# mapleSDuino-V0_1_007-eagle7.net
KiCad netlist of a schematic drawn in EAGLE
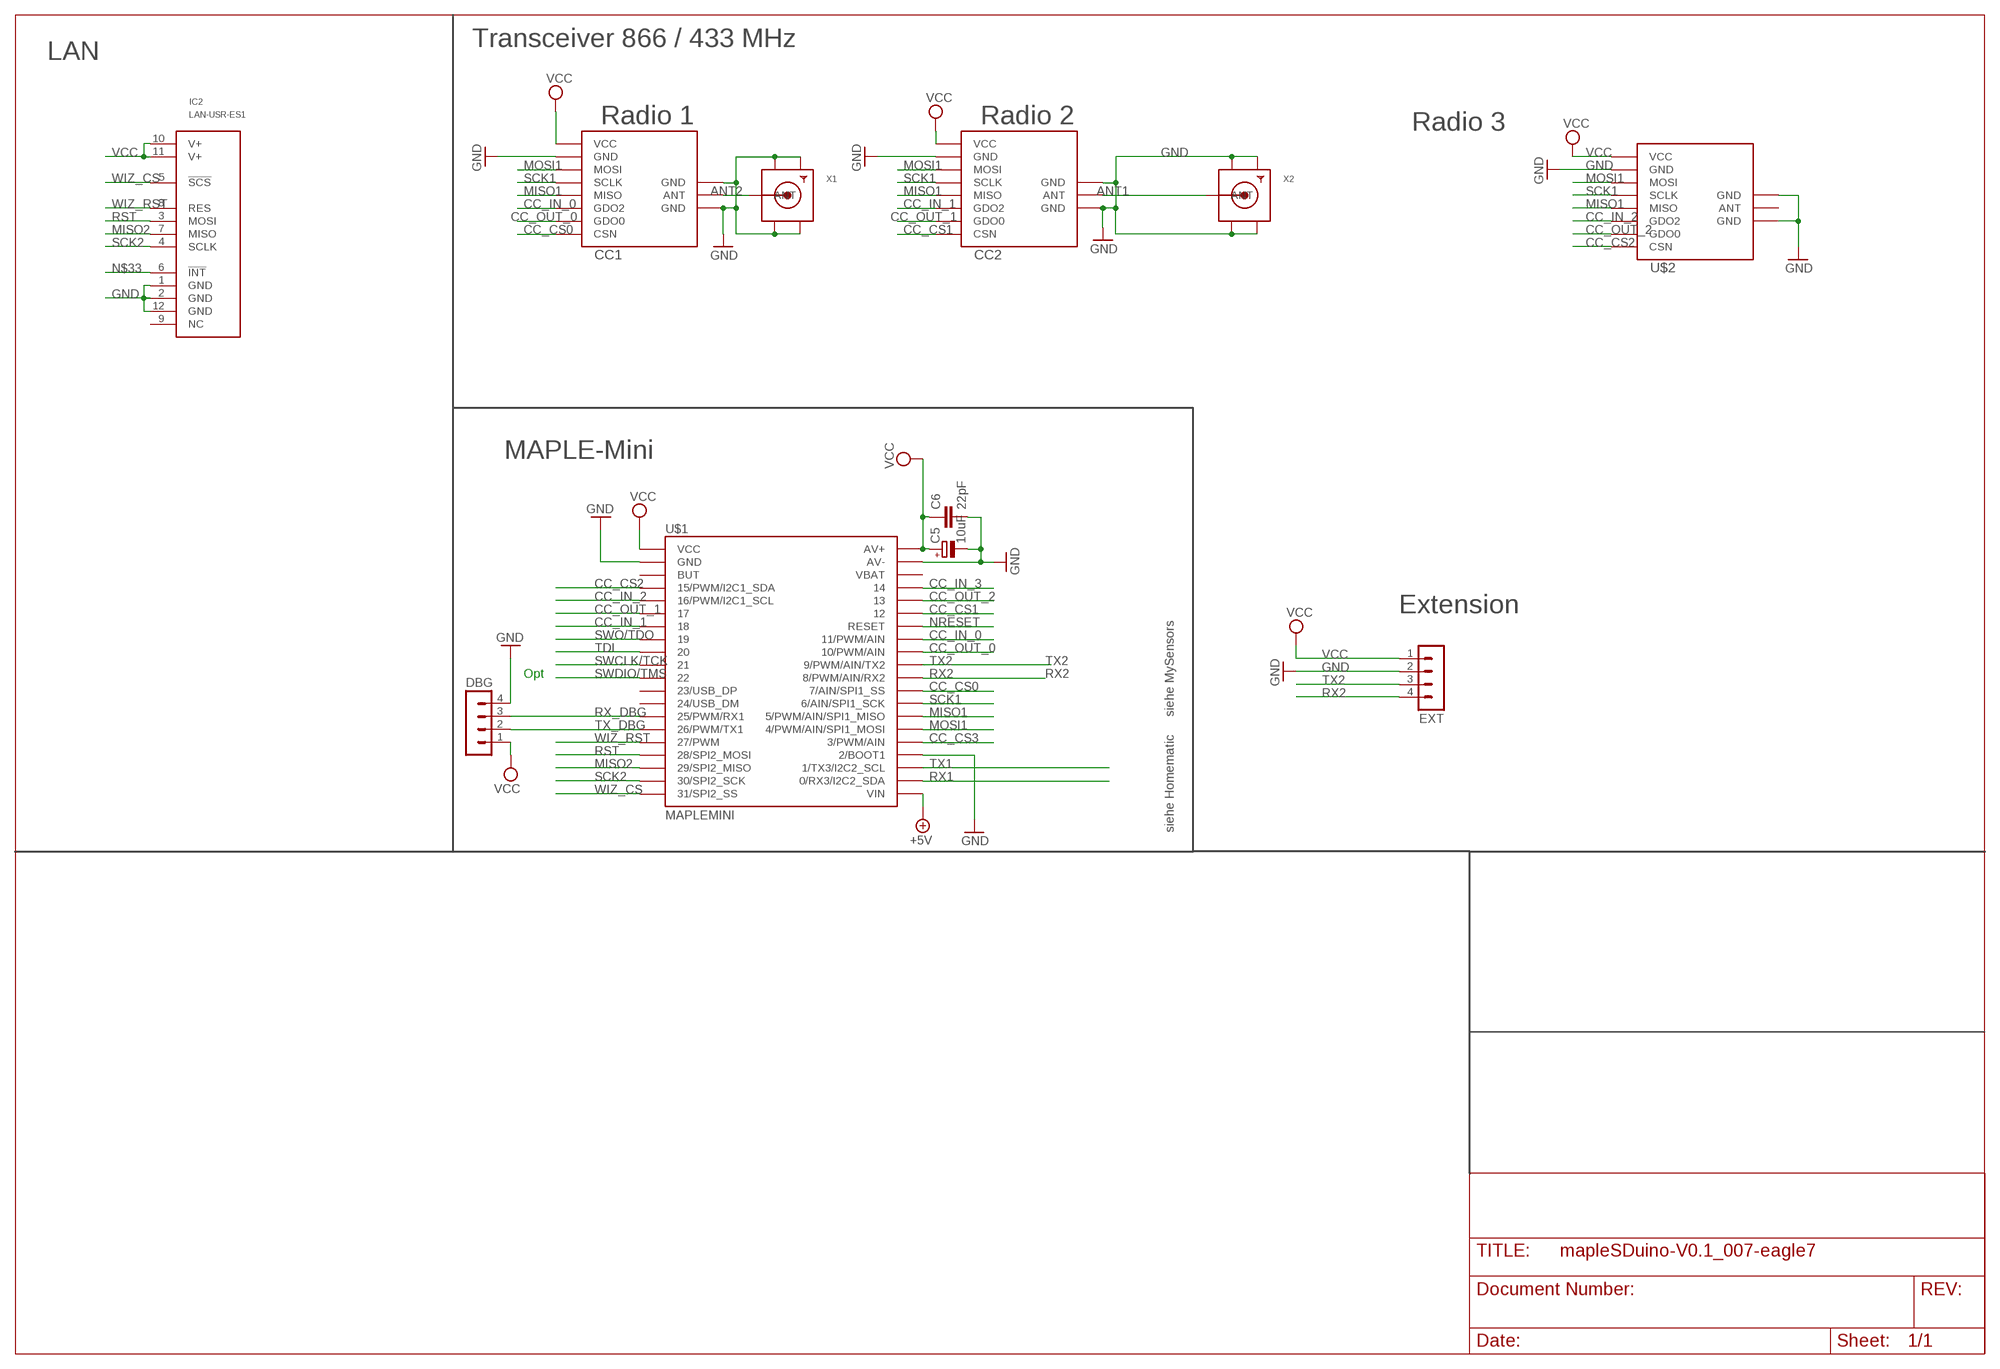
[diagram p0: schematic, sheet 1]

(export (version "E")
  (design (tool "Eeschema 10.0.6"))
  (components
    (comp (ref "C5")
      (value "10uF")
      (footprint "eagle-import:R_2012-12W")
      (libsource (lib "eagle-import") (part "CPOL-EUR/2012-12W"))
    )
    (comp (ref "C6")
      (value "22pF")
      (footprint "eagle-import:C0805")
      (libsource (lib "eagle-import") (part "C-EUC0805"))
    )
    (comp (ref "CC1")
      (value "CC1101")
      (footprint "eagle-import:CC1101_MODULE1_SMD")
      (libsource (lib "eagle-import") (part "wireless_CC1101_MODULE1SMD"))
    )
    (comp (ref "CC2")
      (value "CC1101_MODULE1SMD")
      (footprint "eagle-import:CC1101_MODULE1_SMD")
      (libsource (lib "eagle-import") (part "wireless_CC1101_MODULE1SMD"))
    )
    (comp (ref "DBG")
      (value "MA04-1")
      (footprint "eagle-import:MA04-1")
      (libsource (lib "eagle-import") (part "MA04-1"))
    )
    (comp (ref "EXT")
      (value "MA04-1")
      (footprint "eagle-import:MA04-1")
      (libsource (lib "eagle-import") (part "MA04-1"))
    )
    (comp (ref "IC2")
      (value "LAN-USR-ES1")
      (footprint "eagle-import:USR-ES1")
      (libsource (lib "eagle-import") (part "LAN-USR-ES1"))
    )
    (comp (ref "U$1")
      (value "MAPLEMINI")
      (footprint "eagle-import:20-DIP")
      (libsource (lib "eagle-import") (part "MAPLEMINI"))
    )
    (comp (ref "U$2")
      (value "CC1101_MODULE1DIL_BIG")
      (footprint "eagle-import:CC1101_MODULE1_DIL-2")
      (libsource (lib "eagle-import") (part "CC1101_MODULE1DIL_BIG"))
    )
    (comp (ref "X1")
      (value "SMACONNECTOR_EDGE")
      (footprint "eagle-import:SMA_EDGELAUNCH")
      (libsource (lib "eagle-import") (part "SMACONNECTOR_EDGE"))
    )
    (comp (ref "X2")
      (value "SMACONNECTOR_EDGE")
      (footprint "eagle-import:SMA_EDGELAUNCH")
      (libsource (lib "eagle-import") (part "SMACONNECTOR_EDGE"))
    )
  )
  (nets
    (net (code "1") (name "+5V") (class "Default")
      (node (ref "U$1") (pin "21") (pinfunction "VIN_21") (pintype "bidirectional"))
    )
    (net (code "2") (name "/ANT1") (class "Default")
      (node (ref "CC2") (pin "ANT") (pinfunction "ANT_ANT") (pintype "output"))
      (node (ref "X2") (pin "P") (pinfunction "ANT_P") (pintype "bidirectional"))
    )
    (net (code "3") (name "/ANT2") (class "Default")
      (node (ref "CC1") (pin "ANT") (pinfunction "ANT_ANT") (pintype "output"))
      (node (ref "X1") (pin "P") (pinfunction "ANT_P") (pintype "bidirectional"))
    )
    (net (code "4") (name "/CC_CS0") (class "Default")
      (node (ref "CC1") (pin "CSN") (pinfunction "CSN_CSN") (pintype "bidirectional"))
      (node (ref "U$1") (pin "29") (pinfunction "7/AIN/SPI1_SS_29") (pintype "bidirectional"))
    )
    (net (code "5") (name "/CC_CS1") (class "Default")
      (node (ref "CC2") (pin "CSN") (pinfunction "CSN_CSN") (pintype "bidirectional"))
      (node (ref "U$1") (pin "35") (pinfunction "12_35") (pintype "bidirectional"))
    )
    (net (code "6") (name "/CC_CS2") (class "Default")
      (node (ref "U$1") (pin "4") (pinfunction "15/PWM/I2C1_SDA_4") (pintype "bidirectional"))
      (node (ref "U$2") (pin "8") (pinfunction "CSN_8") (pintype "bidirectional"))
    )
    (net (code "7") (name "/CC_CS3") (class "Default")
      (node (ref "U$1") (pin "25") (pinfunction "3/PWM/AIN_25") (pintype "bidirectional"))
    )
    (net (code "8") (name "/CC_IN_0") (class "Default")
      (node (ref "CC1") (pin "GDO2") (pinfunction "GDO2_GDO2") (pintype "bidirectional"))
      (node (ref "U$1") (pin "33") (pinfunction "11/PWM/AIN_33") (pintype "bidirectional"))
    )
    (net (code "9") (name "/CC_IN_1") (class "Default")
      (node (ref "CC2") (pin "GDO2") (pinfunction "GDO2_GDO2") (pintype "bidirectional"))
      (node (ref "U$1") (pin "7") (pinfunction "18_7") (pintype "bidirectional"))
    )
    (net (code "10") (name "/CC_IN_2") (class "Default")
      (node (ref "U$1") (pin "5") (pinfunction "16/PWM/I2C1_SCL_5") (pintype "bidirectional"))
      (node (ref "U$2") (pin "6") (pinfunction "GDO2_6") (pintype "bidirectional"))
    )
    (net (code "11") (name "/CC_IN_3") (class "Default")
      (node (ref "U$1") (pin "37") (pinfunction "14_37") (pintype "bidirectional"))
    )
    (net (code "12") (name "/CC_OUT_0") (class "Default")
      (node (ref "CC1") (pin "GDO0") (pinfunction "GDO0_GDO0") (pintype "bidirectional"))
      (node (ref "U$1") (pin "32") (pinfunction "10/PWM/AIN_32") (pintype "bidirectional"))
    )
    (net (code "13") (name "/CC_OUT_1") (class "Default")
      (node (ref "CC2") (pin "GDO0") (pinfunction "GDO0_GDO0") (pintype "bidirectional"))
      (node (ref "U$1") (pin "6") (pinfunction "17_6") (pintype "bidirectional"))
    )
    (net (code "14") (name "/CC_OUT_2") (class "Default")
      (node (ref "U$1") (pin "36") (pinfunction "13_36") (pintype "bidirectional"))
      (node (ref "U$2") (pin "7") (pinfunction "GDO0_7") (pintype "bidirectional"))
    )
    (net (code "15") (name "/MISO1") (class "Default")
      (node (ref "CC1") (pin "MISO") (pinfunction "MISO_MISO") (pintype "bidirectional"))
      (node (ref "CC2") (pin "MISO") (pinfunction "MISO_MISO") (pintype "bidirectional"))
      (node (ref "U$1") (pin "27") (pinfunction "5/PWM/AIN/SPI1_MISO_27") (pintype "bidirectional"))
      (node (ref "U$2") (pin "5") (pinfunction "MISO_5") (pintype "bidirectional"))
    )
    (net (code "16") (name "/MISO2") (class "Default")
      (node (ref "IC2") (pin "7") (pinfunction "MISO_7") (pintype "bidirectional"))
      (node (ref "U$1") (pin "18") (pinfunction "29/SPI2_MISO_18") (pintype "bidirectional"))
    )
    (net (code "17") (name "/MOSI1") (class "Default")
      (node (ref "CC1") (pin "MOSI") (pinfunction "MOSI_MOSI") (pintype "bidirectional"))
      (node (ref "CC2") (pin "MOSI") (pinfunction "MOSI_MOSI") (pintype "bidirectional"))
      (node (ref "U$1") (pin "26") (pinfunction "4/PWM/AIN/SPI1_MOSI_26") (pintype "bidirectional"))
      (node (ref "U$2") (pin "3") (pinfunction "MOSI_3") (pintype "bidirectional"))
    )
    (net (code "18") (name "/N$33") (class "Default")
      (node (ref "IC2") (pin "6") (pinfunction "~{INT}_6") (pintype "output"))
    )
    (net (code "19") (name "/NRESET") (class "Default")
      (node (ref "U$1") (pin "34") (pinfunction "RESET_34") (pintype "bidirectional"))
    )
    (net (code "20") (name "/RST") (class "Default")
      (node (ref "IC2") (pin "3") (pinfunction "MOSI_3") (pintype "bidirectional"))
      (node (ref "U$1") (pin "17") (pinfunction "28/SPI2_MOSI_17") (pintype "bidirectional"))
    )
    (net (code "21") (name "/RX1") (class "Default")
      (node (ref "U$1") (pin "22") (pinfunction "0/RX3/I2C2_SDA_22") (pintype "bidirectional"))
    )
    (net (code "22") (name "/RX2") (class "Default")
      (node (ref "EXT") (pin "4") (pinfunction "4_4") (pintype "passive"))
      (node (ref "U$1") (pin "30") (pinfunction "8/PWM/AIN/RX2_30") (pintype "bidirectional"))
    )
    (net (code "23") (name "/RX_DBG") (class "Default")
      (node (ref "DBG") (pin "3") (pinfunction "3_3") (pintype "passive"))
      (node (ref "U$1") (pin "14") (pinfunction "25/PWM/RX1_14") (pintype "bidirectional"))
    )
    (net (code "24") (name "/SCK1") (class "Default")
      (node (ref "CC1") (pin "SCLK") (pinfunction "SCLK_SCLK") (pintype "bidirectional"))
      (node (ref "CC2") (pin "SCLK") (pinfunction "SCLK_SCLK") (pintype "bidirectional"))
      (node (ref "U$1") (pin "28") (pinfunction "6/AIN/SPI1_SCK_28") (pintype "bidirectional"))
      (node (ref "U$2") (pin "4") (pinfunction "SCLK_4") (pintype "bidirectional"))
    )
    (net (code "25") (name "/SCK2") (class "Default")
      (node (ref "IC2") (pin "4") (pinfunction "SCLK_4") (pintype "input"))
      (node (ref "U$1") (pin "19") (pinfunction "30/SPI2_SCK_19") (pintype "bidirectional"))
    )
    (net (code "26") (name "/SWCLK{slash}TCK") (class "Default")
      (node (ref "U$1") (pin "10") (pinfunction "21_10") (pintype "bidirectional"))
    )
    (net (code "27") (name "/SWDIO{slash}TMS") (class "Default")
      (node (ref "U$1") (pin "11") (pinfunction "22_11") (pintype "bidirectional"))
    )
    (net (code "28") (name "/SWO{slash}TDO") (class "Default")
      (node (ref "U$1") (pin "8") (pinfunction "19_8") (pintype "bidirectional"))
    )
    (net (code "29") (name "/TDI") (class "Default")
      (node (ref "U$1") (pin "9") (pinfunction "20_9") (pintype "bidirectional"))
    )
    (net (code "30") (name "/TX1") (class "Default")
      (node (ref "U$1") (pin "23") (pinfunction "1/TX3/I2C2_SCL_23") (pintype "bidirectional"))
    )
    (net (code "31") (name "/TX2") (class "Default")
      (node (ref "EXT") (pin "3") (pinfunction "3_3") (pintype "passive"))
      (node (ref "U$1") (pin "31") (pinfunction "9/PWM/AIN/TX2_31") (pintype "bidirectional"))
    )
    (net (code "32") (name "/TX_DBG") (class "Default")
      (node (ref "DBG") (pin "2") (pinfunction "2_2") (pintype "passive"))
      (node (ref "U$1") (pin "15") (pinfunction "26/PWM/TX1_15") (pintype "bidirectional"))
    )
    (net (code "33") (name "/WIZ_CS") (class "Default")
      (node (ref "IC2") (pin "5") (pinfunction "~{SCS}_5") (pintype "input"))
      (node (ref "U$1") (pin "20") (pinfunction "31/SPI2_SS_20") (pintype "bidirectional"))
    )
    (net (code "34") (name "/WIZ_RST") (class "Default")
      (node (ref "IC2") (pin "8") (pinfunction "RES_8") (pintype "input"))
      (node (ref "U$1") (pin "16") (pinfunction "27/PWM_16") (pintype "bidirectional"))
    )
    (net (code "35") (name "GND") (class "Default")
      (node (ref "C5") (pin "-") (pinfunction "-_-") (pintype "passive"))
      (node (ref "C6") (pin "2") (pinfunction "2_2") (pintype "passive"))
      (node (ref "CC1") (pin "GND@0") (pinfunction "GND_GND@0") (pintype "power_in"))
      (node (ref "CC1") (pin "GND@1") (pinfunction "GND_GND@1") (pintype "power_in"))
      (node (ref "CC1") (pin "GND@2") (pinfunction "GND_GND@2") (pintype "power_in"))
      (node (ref "CC2") (pin "GND@0") (pinfunction "GND_GND@0") (pintype "power_in"))
      (node (ref "CC2") (pin "GND@1") (pinfunction "GND_GND@1") (pintype "power_in"))
      (node (ref "CC2") (pin "GND@2") (pinfunction "GND_GND@2") (pintype "power_in"))
      (node (ref "DBG") (pin "4") (pinfunction "4_4") (pintype "passive"))
      (node (ref "EXT") (pin "2") (pinfunction "2_2") (pintype "passive"))
      (node (ref "IC2") (pin "1") (pinfunction "GND_1") (pintype "power_in"))
      (node (ref "IC2") (pin "12") (pinfunction "GND_12") (pintype "power_in"))
      (node (ref "IC2") (pin "2") (pinfunction "GND_2") (pintype "power_in"))
      (node (ref "U$1") (pin "2") (pinfunction "GND_2") (pintype "bidirectional"))
      (node (ref "U$1") (pin "24") (pinfunction "2/BOOT1_24") (pintype "bidirectional"))
      (node (ref "U$1") (pin "39") (pinfunction "AV-_39") (pintype "bidirectional"))
      (node (ref "U$2") (pin "11") (pinfunction "GND_11") (pintype "power_in"))
      (node (ref "U$2") (pin "2") (pinfunction "GND_2") (pintype "power_in"))
      (node (ref "U$2") (pin "9") (pinfunction "GND_9") (pintype "power_in"))
      (node (ref "X1") (pin "GND@1") (pinfunction "GND4_GND@1") (pintype "power_in"))
      (node (ref "X1") (pin "GND@2") (pinfunction "GND3_GND@2") (pintype "power_in"))
      (node (ref "X1") (pin "GND@3") (pinfunction "GND2_GND@3") (pintype "power_in"))
      (node (ref "X1") (pin "GND@4") (pinfunction "GND1_GND@4") (pintype "power_in"))
      (node (ref "X2") (pin "GND@1") (pinfunction "GND4_GND@1") (pintype "power_in"))
      (node (ref "X2") (pin "GND@2") (pinfunction "GND3_GND@2") (pintype "power_in"))
      (node (ref "X2") (pin "GND@3") (pinfunction "GND2_GND@3") (pintype "power_in"))
      (node (ref "X2") (pin "GND@4") (pinfunction "GND1_GND@4") (pintype "power_in"))
    )
    (net (code "36") (name "VCC") (class "Default")
      (node (ref "C5") (pin "+") (pinfunction "+_+") (pintype "passive"))
      (node (ref "C6") (pin "1") (pinfunction "1_1") (pintype "passive"))
      (node (ref "CC1") (pin "VCC") (pinfunction "VCC_VCC") (pintype "power_in"))
      (node (ref "CC2") (pin "VCC") (pinfunction "VCC_VCC") (pintype "power_in"))
      (node (ref "DBG") (pin "1") (pinfunction "1_1") (pintype "passive"))
      (node (ref "EXT") (pin "1") (pinfunction "1_1") (pintype "passive"))
      (node (ref "IC2") (pin "10") (pinfunction "V+_10") (pintype "power_in"))
      (node (ref "IC2") (pin "11") (pinfunction "V+_11") (pintype "power_in"))
      (node (ref "U$1") (pin "1") (pinfunction "VCC_1") (pintype "bidirectional"))
      (node (ref "U$1") (pin "40") (pinfunction "AV+_40") (pintype "bidirectional"))
      (node (ref "U$2") (pin "1") (pinfunction "VCC_1") (pintype "power_in"))
    )
    (net (code "37") (name "unconnected-(IC2-NC-Pad9)") (class "Default")
      (node (ref "IC2") (pin "9") (pinfunction "NC_9") (pintype "no_connect"))
    )
    (net (code "38") (name "unconnected-(U$1-23{slash}USB_DP-Pad12)") (class "Default")
      (node (ref "U$1") (pin "12") (pinfunction "23/USB_DP_12") (pintype "bidirectional"))
    )
    (net (code "39") (name "unconnected-(U$1-24{slash}USB_DM-Pad13)") (class "Default")
      (node (ref "U$1") (pin "13") (pinfunction "24/USB_DM_13") (pintype "bidirectional"))
    )
    (net (code "40") (name "unconnected-(U$1-BUT-Pad3)") (class "Default")
      (node (ref "U$1") (pin "3") (pinfunction "BUT_3") (pintype "bidirectional"))
    )
    (net (code "41") (name "unconnected-(U$1-VBAT-Pad38)") (class "Default")
      (node (ref "U$1") (pin "38") (pinfunction "VBAT_38") (pintype "bidirectional"))
    )
    (net (code "42") (name "unconnected-(U$2-ANT-Pad10)") (class "Default")
      (node (ref "U$2") (pin "10") (pinfunction "ANT_10") (pintype "output"))
    )
  )
)
